# tablo_tara3.net
KiCad netlist of a schematic drawn in Altium Designer
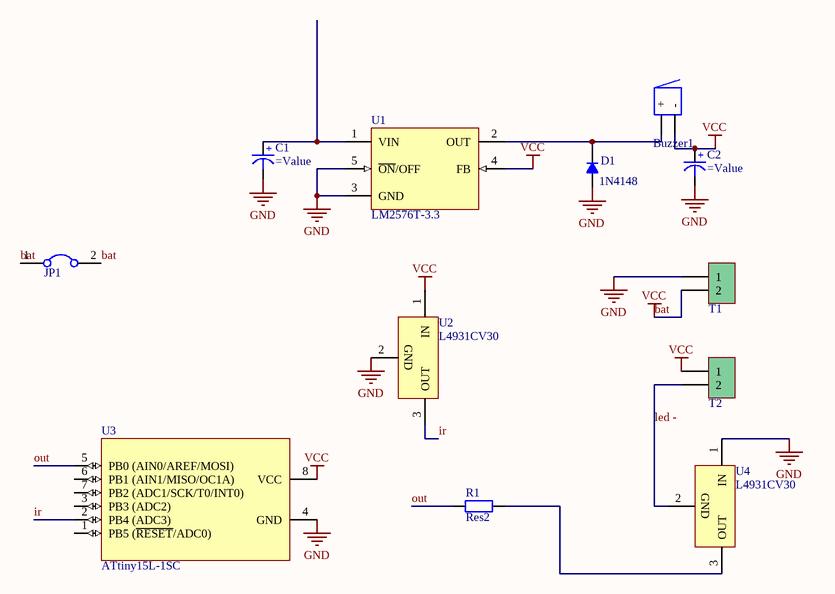
[diagram p0: tablo tara3.SchDoc]

(export (version "E")
  (design (tool "Eeschema 10.0.6"))
  (components
    (comp (ref "Buzzer1")
      (value "Buzzer")
      (footprint "BUZZER")
      (fields (field (name "DESIGNER") "Seyed Mohsen Ghasemain"))
      (libsource (lib "PicPars.com_usefully_Library") (part "Buzzer"))
    )
    (comp (ref "C1")
      (value "~")
      (footprint "ELEC-CAP-RAD10-20")
      (description "Electrolytic Capacitor")
      (libsource (lib "AltiumLib1") (part "Capacitor Electrolytic"))
    )
    (comp (ref "C2")
      (value "~")
      (footprint "ELEC-CAP-RAD10-20")
      (description "Electrolytic Capacitor")
      (libsource (lib "AltiumLib1") (part "Capacitor Electrolytic"))
    )
    (comp (ref "D1")
      (value "MODEL")
      (footprint "DO-41")
      (description "Diode")
      (fields (field (name "MODEL") "1N4148"))
      (libsource (lib "AltiumLib1") (part "Diode"))
    )
    (comp (ref "JP1")
      (value "Jumper")
      (footprint "Header 2X1")
      (libsource (lib "AltiumLib1") (part "Jumper"))
    )
    (comp (ref "R1")
      (value "Res2")
      (footprint "Res50")
      (description "Resistor")
      (fields (field (name "PUBLISHER") "Altium Limited"))
      (libsource (lib "Miscellaneous Devices") (part "Res50"))
    )
    (comp (ref "T1")
      (value "Phoenix terminal")
      (footprint "phoenix terminal 2")
      (description "Terminal 2 Pin")
      (fields (field (name "DESIGNER") "Seyed Mohsen Ghasemain") (field (name "E-MAIL") "picpars@gmail.com"))
      (libsource (lib "PicPars.com_usefully_Library") (part "Phoenix terminal 2"))
    )
    (comp (ref "T2")
      (value "Phoenix terminal")
      (footprint "phoenix terminal 2")
      (description "Terminal 2 Pin")
      (fields (field (name "DESIGNER") "Seyed Mohsen Ghasemain") (field (name "E-MAIL") "picpars@gmail.com"))
      (libsource (lib "PicPars.com_usefully_Library") (part "Phoenix terminal 2"))
    )
    (comp (ref "U1")
      (value "LM2576T-3.3")
      (footprint "T05A")
      (description "SIMPLE SWITCHER; 3A Step-Down Voltage Regulator")
      (fields
        (field (name "MANUFACTURER") "National Semiconductor")
        (field (name "DIGIKEYPARTNUMBER") "LM2576T-3.3NS-ND")
        (field (name "PUBLISHER") "Altium Limited")
      )
      (libsource (lib "NSC Switcher") (part "LM2576T-3.3"))
    )
    (comp (ref "U2")
      (value "L4931CV30")
      (footprint "TO-220A")
      (description "250mA, Very Low Drop ( 0.4V) Voltage Regulator")
      (fields (field (name "PUBLISHER") "Altium Limited"))
      (libsource (lib "ST Power Mgt Voltage Regulator") (part "L4931CV30"))
    )
    (comp (ref "U3")
      (value "ATtiny15L-1SC")
      (footprint "8S2_N")
      (description "8-Bit AVR Microcontroller with 1K Byte of Flash Memory")
      (fields (field (name "PUBLISHER") "Altium Limited"))
      (libsource (lib "Atmel Microcontroller 8-Bit AVR") (part "ATtiny15L-1SC"))
    )
    (comp (ref "U4")
      (value "L4931CV30")
      (footprint "TO-220A")
      (description "250mA, Very Low Drop ( 0.4V) Voltage Regulator")
      (fields (field (name "PUBLISHER") "Altium Limited"))
      (libsource (lib "ST Power Mgt Voltage Regulator") (part "L4931CV30"))
    )
  )
  (nets
    (net (code "1") (name "/ir") (class "Default")
      (node (ref "U2") (pin "3") (pinfunction "OUT_3") (pintype "power_in"))
      (node (ref "U3") (pin "2") (pinfunction "PB4_(ADC3)_2") (pintype "bidirectional"))
    )
    (net (code "2") (name "/led -") (class "Default")
      (node (ref "T2") (pin "2") (pinfunction "2_2") (pintype "passive"))
      (node (ref "U4") (pin "2") (pinfunction "GND_2") (pintype "power_in"))
    )
    (net (code "3") (name "/out") (class "Default")
      (node (ref "R1") (pin "1") (pinfunction "1_1") (pintype "passive"))
      (node (ref "U3") (pin "5") (pinfunction "PB0_(AIN0/AREF/MOSI)_5") (pintype "bidirectional"))
    )
    (net (code "4") (name "GND") (class "Default")
      (node (ref "C1") (pin "1") (pinfunction "-_1") (pintype "passive"))
      (node (ref "C2") (pin "1") (pinfunction "-_1") (pintype "passive"))
      (node (ref "D1") (pin "1") (pinfunction "A_1") (pintype "passive"))
      (node (ref "T1") (pin "1") (pinfunction "1_1") (pintype "passive"))
      (node (ref "U1") (pin "3") (pinfunction "GND_3") (pintype "power_in"))
      (node (ref "U1") (pin "5") (pinfunction "~{ON}/OFF_5") (pintype "input"))
      (node (ref "U2") (pin "2") (pinfunction "GND_2") (pintype "power_in"))
      (node (ref "U3") (pin "4") (pinfunction "GND_4") (pintype "power_in"))
      (node (ref "U4") (pin "1") (pinfunction "IN_1") (pintype "power_in"))
    )
    (net (code "5") (name "Net-(Buzzer1-+)") (class "Default")
      (node (ref "Buzzer1") (pin "1") (pinfunction "+_1") (pintype "passive"))
      (node (ref "D1") (pin "2") (pinfunction "K_2") (pintype "passive"))
      (node (ref "U1") (pin "2") (pinfunction "OUT_2") (pintype "power_in"))
    )
    (net (code "6") (name "Net-(C1-+)") (class "Default")
      (node (ref "C1") (pin "2") (pinfunction "+_2") (pintype "passive"))
      (node (ref "U1") (pin "1") (pinfunction "VIN_1") (pintype "power_in"))
    )
    (net (code "7") (name "Net-(U4-OUT)") (class "Default")
      (node (ref "R1") (pin "2") (pinfunction "2_2") (pintype "passive"))
      (node (ref "U4") (pin "3") (pinfunction "OUT_3") (pintype "power_in"))
    )
    (net (code "8") (name "VCC") (class "Default")
      (node (ref "Buzzer1") (pin "2") (pinfunction "-_2") (pintype "passive"))
      (node (ref "C2") (pin "2") (pinfunction "+_2") (pintype "passive"))
      (node (ref "JP1") (pin "1") (pinfunction "1_1") (pintype "passive"))
      (node (ref "JP1") (pin "2") (pinfunction "2_2") (pintype "passive"))
      (node (ref "T1") (pin "2") (pinfunction "2_2") (pintype "passive"))
      (node (ref "T2") (pin "1") (pinfunction "1_1") (pintype "passive"))
      (node (ref "U1") (pin "4") (pinfunction "FB_4") (pintype "input"))
      (node (ref "U2") (pin "1") (pinfunction "IN_1") (pintype "power_in"))
      (node (ref "U3") (pin "8") (pinfunction "VCC_8") (pintype "power_in"))
    )
    (net (code "9") (name "unconnected-(U3-PB1_(AIN1{slash}MISO{slash}OC1A)-Pad6)") (class "Default")
      (node (ref "U3") (pin "6") (pinfunction "PB1_(AIN1/MISO/OC1A)_6") (pintype "bidirectional"))
    )
    (net (code "10") (name "unconnected-(U3-PB2_(ADC1{slash}SCK{slash}T0{slash}INT0)-Pad7)") (class "Default")
      (node (ref "U3") (pin "7") (pinfunction "PB2_(ADC1/SCK/T0/INT0)_7") (pintype "bidirectional"))
    )
    (net (code "11") (name "unconnected-(U3-PB3_(ADC2)-Pad3)") (class "Default")
      (node (ref "U3") (pin "3") (pinfunction "PB3_(ADC2)_3") (pintype "bidirectional"))
    )
    (net (code "12") (name "unconnected-(U3-PB5_(~{RESET}{slash}ADC0)-Pad1)") (class "Default")
      (node (ref "U3") (pin "1") (pinfunction "PB5_(~{RESET}/ADC0)_1") (pintype "bidirectional"))
    )
  )
)
